# 2021-07-02_OrangeHat.net
KiCad netlist of a schematic drawn in EAGLE
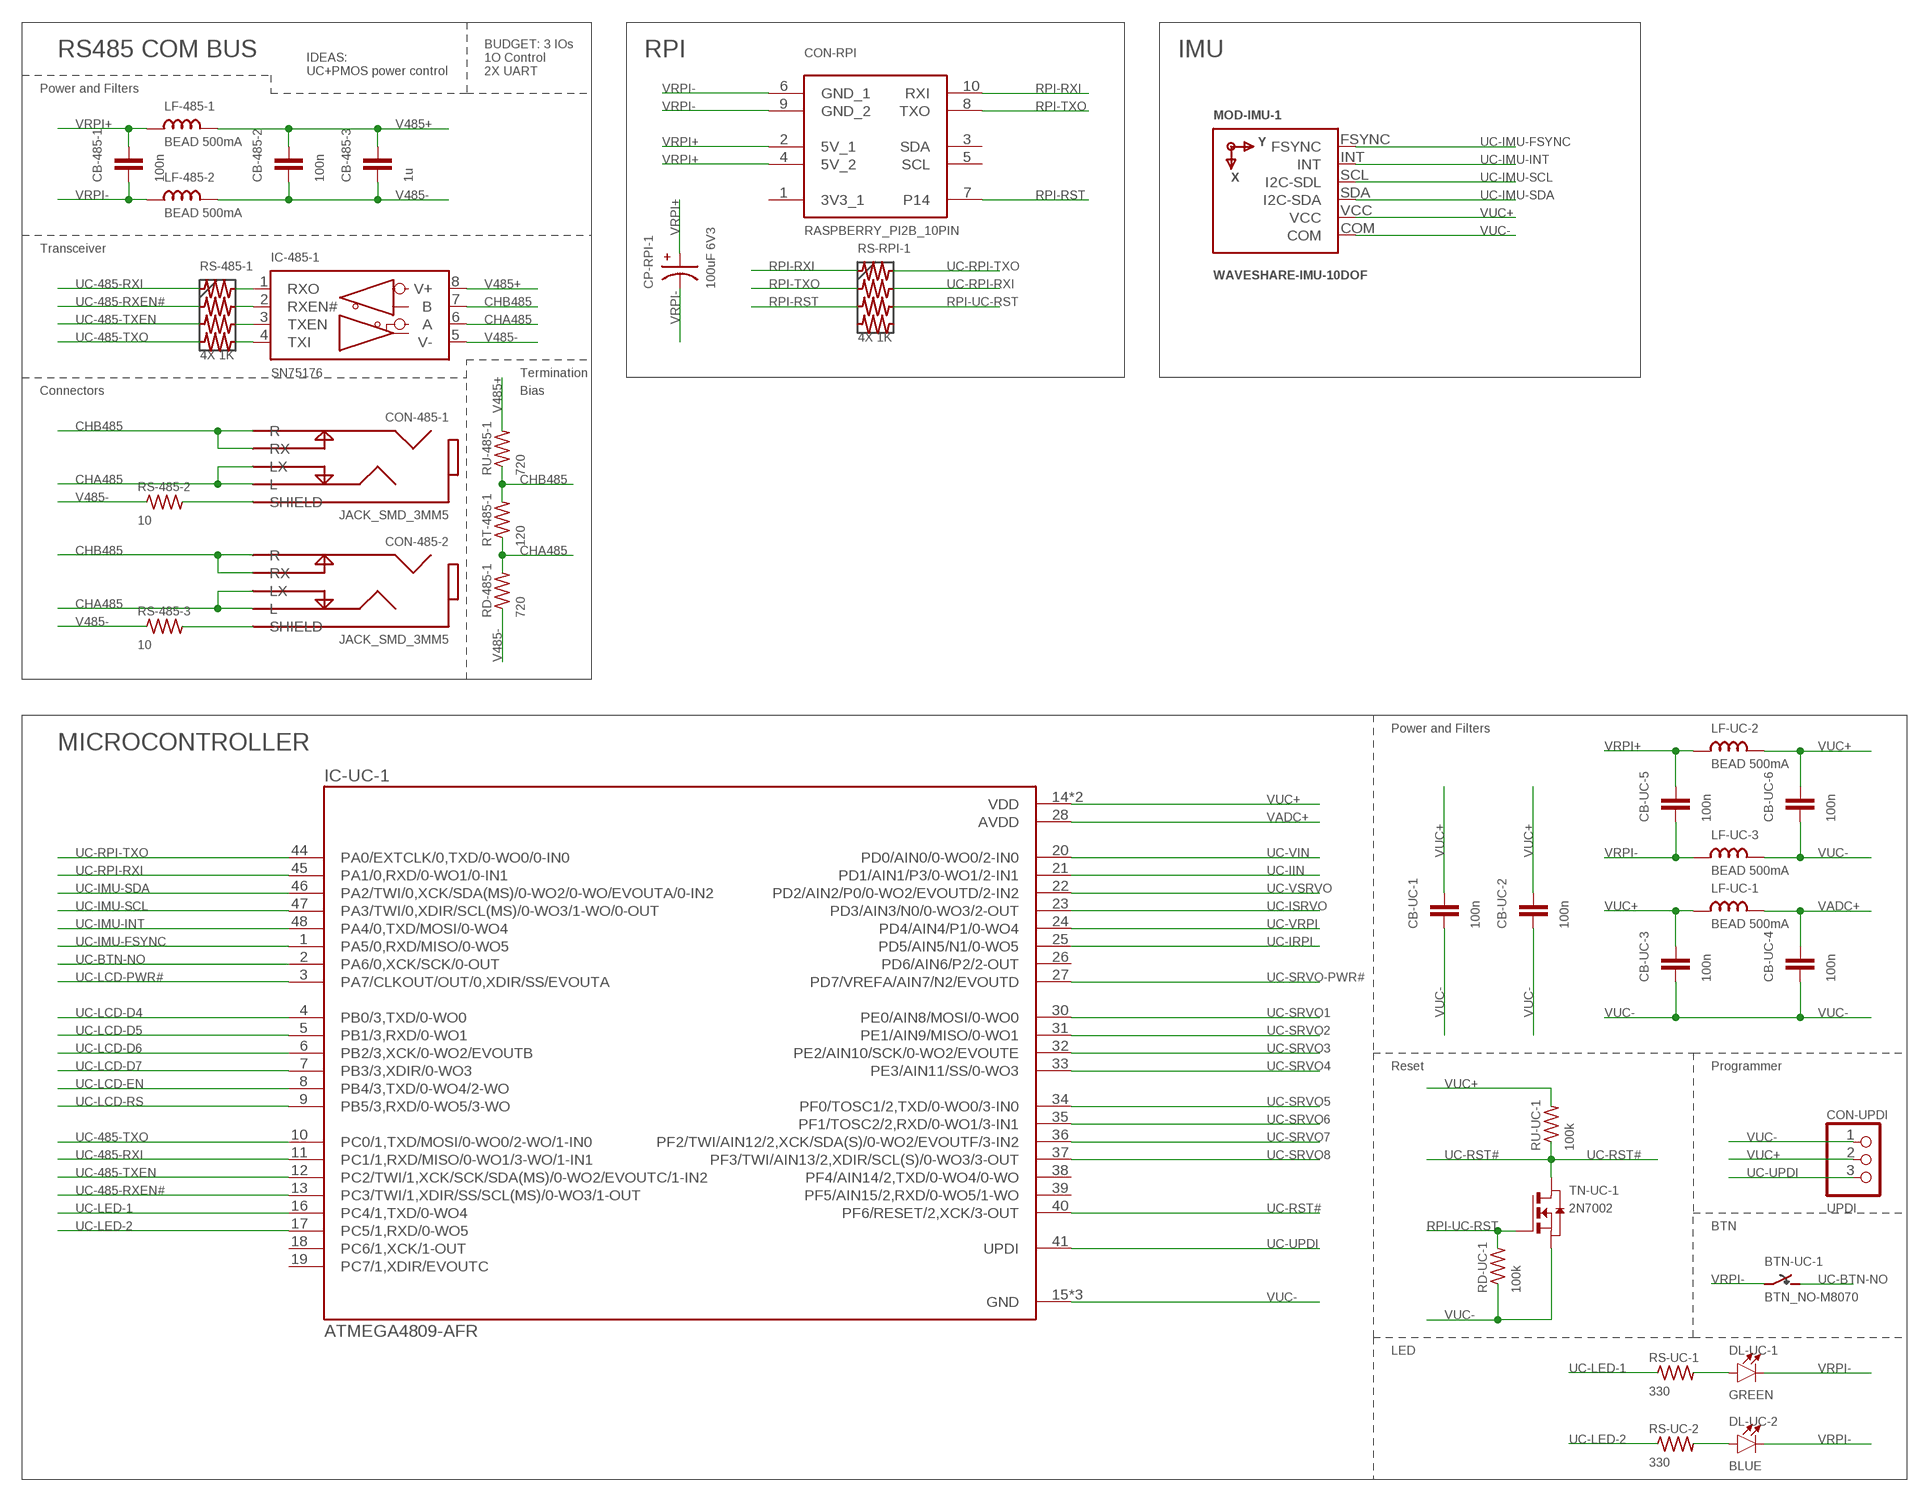
[diagram p0: schematic, sheet 1, part 1 of 2]
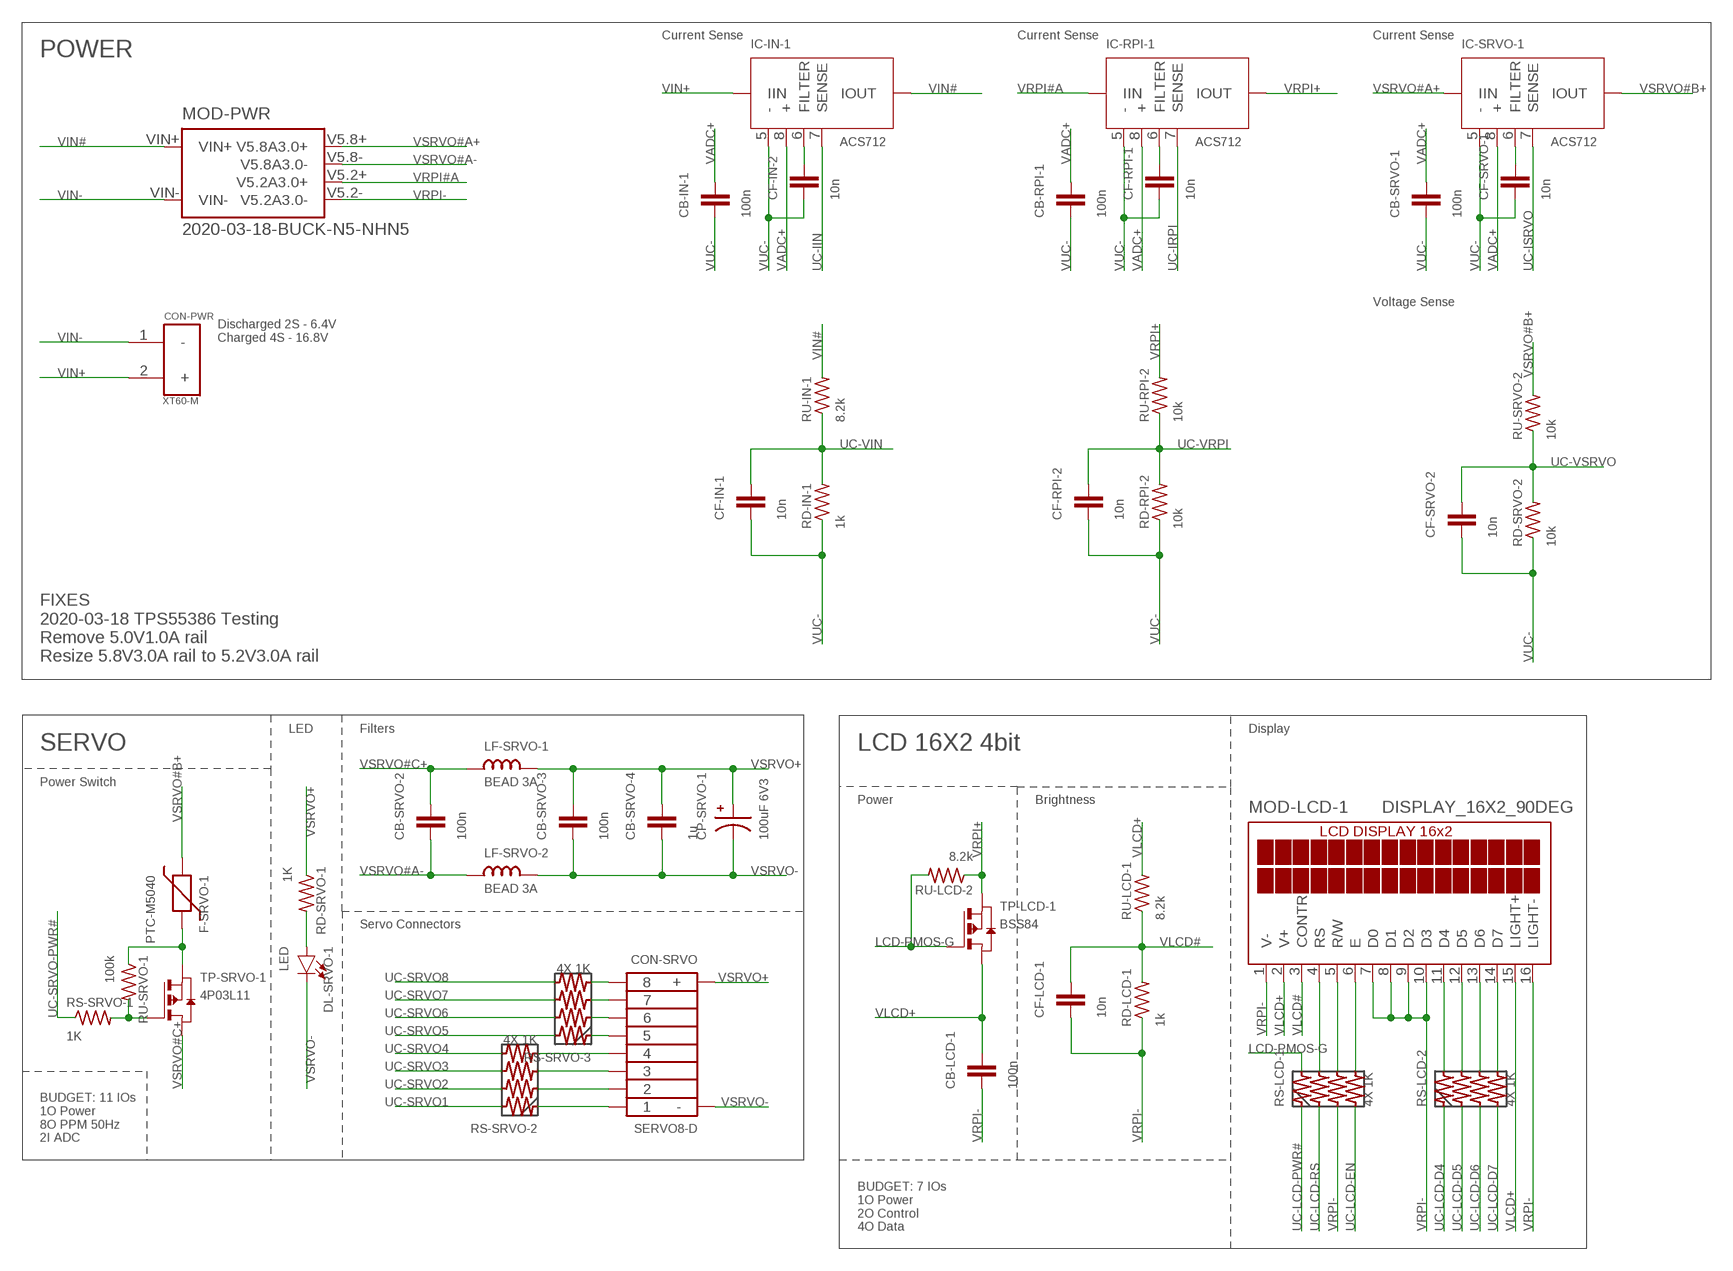
[diagram p1: schematic, sheet 1, part 2 of 2]

(export (version "E")
  (design (tool "Eeschema 10.0.6"))
  (components
    (comp (ref "BTN-UC-1")
      (value "BTN_NO-M8070")
      (footprint "eagle-import:SMD_BTN_M8070")
      (libsource (lib "eagle-import") (part "BTN_NO-M8070"))
    )
    (comp (ref "CB-485-1")
      (value "100n")
      (footprint "eagle-import:SMD-M2012")
      (libsource (lib "eagle-import") (part "C-NPOL"))
    )
    (comp (ref "CB-485-2")
      (value "100n")
      (footprint "eagle-import:SMD-M2012")
      (libsource (lib "eagle-import") (part "C-NPOL"))
    )
    (comp (ref "CB-485-3")
      (value "1u")
      (footprint "eagle-import:SMD-M2012")
      (libsource (lib "eagle-import") (part "C-NPOL"))
    )
    (comp (ref "CB-IN-1")
      (value "100n")
      (footprint "eagle-import:SMD-M2012")
      (libsource (lib "eagle-import") (part "C-NPOL"))
    )
    (comp (ref "CB-LCD-1")
      (value "100n")
      (footprint "eagle-import:SMD-M2012")
      (libsource (lib "eagle-import") (part "C-NPOL"))
    )
    (comp (ref "CB-RPI-1")
      (value "100n")
      (footprint "eagle-import:SMD-M2012")
      (libsource (lib "eagle-import") (part "C-NPOL"))
    )
    (comp (ref "CB-SRVO-1")
      (value "100n")
      (footprint "eagle-import:SMD-M2012")
      (libsource (lib "eagle-import") (part "C-NPOL"))
    )
    (comp (ref "CB-SRVO-2")
      (value "100n")
      (footprint "eagle-import:SMD-M2012")
      (libsource (lib "eagle-import") (part "C-NPOL"))
    )
    (comp (ref "CB-SRVO-3")
      (value "100n")
      (footprint "eagle-import:SMD-M2012")
      (libsource (lib "eagle-import") (part "C-NPOL"))
    )
    (comp (ref "CB-SRVO-4")
      (value "1u")
      (footprint "eagle-import:SMD-M2012")
      (libsource (lib "eagle-import") (part "C-NPOL"))
    )
    (comp (ref "CB-UC-1")
      (value "100n")
      (footprint "eagle-import:SMD-M2012")
      (libsource (lib "eagle-import") (part "C-NPOL"))
    )
    (comp (ref "CB-UC-2")
      (value "100n")
      (footprint "eagle-import:SMD-M2012")
      (libsource (lib "eagle-import") (part "C-NPOL"))
    )
    (comp (ref "CB-UC-3")
      (value "100n")
      (footprint "eagle-import:SMD-M2012")
      (libsource (lib "eagle-import") (part "C-NPOL"))
    )
    (comp (ref "CB-UC-4")
      (value "100n")
      (footprint "eagle-import:SMD-M2012")
      (libsource (lib "eagle-import") (part "C-NPOL"))
    )
    (comp (ref "CB-UC-5")
      (value "100n")
      (footprint "eagle-import:SMD-M2012")
      (libsource (lib "eagle-import") (part "C-NPOL"))
    )
    (comp (ref "CB-UC-6")
      (value "100n")
      (footprint "eagle-import:SMD-M2012")
      (libsource (lib "eagle-import") (part "C-NPOL"))
    )
    (comp (ref "CF-IN-1")
      (value "10n")
      (footprint "eagle-import:SMD-M2012")
      (libsource (lib "eagle-import") (part "C-NPOL"))
    )
    (comp (ref "CF-IN-2")
      (value "10n")
      (footprint "eagle-import:SMD-M2012")
      (libsource (lib "eagle-import") (part "C-NPOL"))
    )
    (comp (ref "CF-LCD-1")
      (value "10n")
      (footprint "eagle-import:SMD-M2012")
      (libsource (lib "eagle-import") (part "C-NPOL"))
    )
    (comp (ref "CF-RPI-1")
      (value "10n")
      (footprint "eagle-import:SMD-M2012")
      (libsource (lib "eagle-import") (part "C-NPOL"))
    )
    (comp (ref "CF-RPI-2")
      (value "10n")
      (footprint "eagle-import:SMD-M2012")
      (libsource (lib "eagle-import") (part "C-NPOL"))
    )
    (comp (ref "CF-SRVO-1")
      (value "10n")
      (footprint "eagle-import:SMD-M2012")
      (libsource (lib "eagle-import") (part "C-NPOL"))
    )
    (comp (ref "CF-SRVO-2")
      (value "10n")
      (footprint "eagle-import:SMD-M2012")
      (libsource (lib "eagle-import") (part "C-NPOL"))
    )
    (comp (ref "CON-485-1")
      (value "JACK_SMD_3MM5")
      (footprint "eagle-import:JACK_SMD_3MM5")
      (libsource (lib "eagle-import") (part "JACK_SMD_3MM5"))
    )
    (comp (ref "CON-485-2")
      (value "JACK_SMD_3MM5")
      (footprint "eagle-import:JACK_SMD_3MM5")
      (libsource (lib "eagle-import") (part "JACK_SMD_3MM5"))
    )
    (comp (ref "CON-PWR")
      (value "XT60-M")
      (footprint "eagle-import:AMASS_XT60-M")
      (fields (field (name "MF") "AMASS"))
      (libsource (lib "eagle-import") (part "XT60-M"))
    )
    (comp (ref "CON-RPI")
      (value "RASPBERRY_PI2B_10PIN")
      (footprint "eagle-import:RASPBERRY_PI2B_10PIN")
      (libsource (lib "eagle-import") (part "RASPBERRY_PI2B_10PIN"))
    )
    (comp (ref "CON-SRVO")
      (value "SERVO8-D")
      (footprint "eagle-import:SERVO8#")
      (libsource (lib "eagle-import") (part "SERVO8-D"))
    )
    (comp (ref "CON-UPDI")
      (value "UPDI")
      (footprint "eagle-import:1X03")
      (libsource (lib "eagle-import") (part "PINHD-1X3"))
    )
    (comp (ref "CP-RPI-1")
      (value "100uF 6V3")
      (footprint "eagle-import:E2,5-5")
      (libsource (lib "eagle-import") (part "C-POLE2.5-5"))
    )
    (comp (ref "CP-SRVO-1")
      (value "100uF 6V3")
      (footprint "eagle-import:E2,5-5")
      (libsource (lib "eagle-import") (part "C-POLE2.5-5"))
    )
    (comp (ref "DL-SRVO-1")
      (value "LED")
      (footprint "eagle-import:SMD-M2012-POL")
      (libsource (lib "eagle-import") (part "LED"))
    )
    (comp (ref "DL-UC-1")
      (value "GREEN")
      (footprint "eagle-import:SMD-M2012-POL")
      (libsource (lib "eagle-import") (part "LED"))
    )
    (comp (ref "DL-UC-2")
      (value "BLUE")
      (footprint "eagle-import:SMD-M2012-POL")
      (libsource (lib "eagle-import") (part "LED"))
    )
    (comp (ref "F-SRVO-1")
      (value "PTC-M5040")
      (footprint "eagle-import:SMD-M5040")
      (libsource (lib "eagle-import") (part "PTC-M5040"))
    )
    (comp (ref "IC-485-1")
      (value "SN75176")
      (footprint "eagle-import:DIL08")
      (fields (field (name "MPN") "MAX481CPA+"))
      (libsource (lib "eagle-import") (part "RS485"))
    )
    (comp (ref "IC-IN-1")
      (value "ACS712")
      (footprint "eagle-import:SO8")
      (libsource (lib "eagle-import") (part "ACS712"))
    )
    (comp (ref "IC-RPI-1")
      (value "ACS712")
      (footprint "eagle-import:SO8")
      (libsource (lib "eagle-import") (part "ACS712"))
    )
    (comp (ref "IC-SRVO-1")
      (value "ACS712")
      (footprint "eagle-import:SO8")
      (libsource (lib "eagle-import") (part "ACS712"))
    )
    (comp (ref "IC-UC-1")
      (value "ATMEGA4809-AFR")
      (footprint "eagle-import:QFP50P900X900X120-48N")
      (fields (field (name "MF") "Microchip"))
      (libsource (lib "eagle-import") (part "ATMEGA4809-AFR"))
    )
    (comp (ref "LF-485-1")
      (value "BEAD 500mA")
      (footprint "eagle-import:SMD-M2012")
      (libsource (lib "eagle-import") (part "L-M2012"))
    )
    (comp (ref "LF-485-2")
      (value "BEAD 500mA")
      (footprint "eagle-import:SMD-M2012")
      (libsource (lib "eagle-import") (part "L-M2012"))
    )
    (comp (ref "LF-SRVO-1")
      (value "BEAD 3A")
      (footprint "eagle-import:SMD-M2016")
      (libsource (lib "eagle-import") (part "L-M2016"))
    )
    (comp (ref "LF-SRVO-2")
      (value "BEAD 3A")
      (footprint "eagle-import:SMD-M2016")
      (libsource (lib "eagle-import") (part "L-M2016"))
    )
    (comp (ref "LF-UC-1")
      (value "BEAD 500mA")
      (footprint "eagle-import:SMD-M2012")
      (libsource (lib "eagle-import") (part "L-M2012"))
    )
    (comp (ref "LF-UC-2")
      (value "BEAD 500mA")
      (footprint "eagle-import:SMD-M2012")
      (libsource (lib "eagle-import") (part "L-M2012"))
    )
    (comp (ref "LF-UC-3")
      (value "BEAD 500mA")
      (footprint "eagle-import:SMD-M2012")
      (libsource (lib "eagle-import") (part "L-M2012"))
    )
    (comp (ref "MOD-IMU-1")
      (value "WAVESHARE-IMU-10DOF")
      (footprint "eagle-import:WAVESHARE-IMU-10DOF")
      (libsource (lib "eagle-import") (part "WAVESHARE-IMU-10DOF"))
    )
    (comp (ref "MOD-LCD-1")
      (value "DISPLAY_16X2_90DEG")
      (footprint "eagle-import:DISPLAY_16X2_90DEG")
      (libsource (lib "eagle-import") (part "DISPLAY_16X2_90DEG"))
    )
    (comp (ref "MOD-PWR")
      (value "2020-03-18-BUCK-N5-NHN5")
      (footprint "eagle-import:2020-03-18-BUCK-NHN5")
      (libsource (lib "eagle-import") (part "2020-03-18-BUCK-N5-NHN5"))
    )
    (comp (ref "RD-485-1")
      (value "720")
      (footprint "eagle-import:TH-2MM54-V")
      (libsource (lib "eagle-import") (part "R0207/2V"))
    )
    (comp (ref "RD-IN-1")
      (value "1k")
      (footprint "eagle-import:SMD-M2012")
      (libsource (lib "eagle-import") (part "R-M2012"))
    )
    (comp (ref "RD-LCD-1")
      (value "1k")
      (footprint "eagle-import:SMD-M2012")
      (libsource (lib "eagle-import") (part "R-M2012"))
    )
    (comp (ref "RD-RPI-2")
      (value "10k")
      (footprint "eagle-import:SMD-M2012")
      (libsource (lib "eagle-import") (part "R-M2012"))
    )
    (comp (ref "RD-SRVO-1")
      (value "1K")
      (footprint "eagle-import:SMD-M2012")
      (libsource (lib "eagle-import") (part "R-M2012"))
    )
    (comp (ref "RD-SRVO-2")
      (value "10k")
      (footprint "eagle-import:SMD-M2012")
      (libsource (lib "eagle-import") (part "R-M2012"))
    )
    (comp (ref "RD-UC-1")
      (value "100k")
      (footprint "eagle-import:SMD-M2012")
      (libsource (lib "eagle-import") (part "R-M2012"))
    )
    (comp (ref "RS-485-1")
      (value "4X 1K")
      (footprint "eagle-import:RAC1206")
      (libsource (lib "eagle-import") (part "RAC164"))
    )
    (comp (ref "RS-485-2")
      (value "10")
      (footprint "eagle-import:SMD-M2012")
      (libsource (lib "eagle-import") (part "R-M2012"))
    )
    (comp (ref "RS-485-3")
      (value "10")
      (footprint "eagle-import:SMD-M2012")
      (libsource (lib "eagle-import") (part "R-M2012"))
    )
    (comp (ref "RS-LCD-1")
      (value "4X 1K")
      (footprint "eagle-import:RAC1206")
      (libsource (lib "eagle-import") (part "RAC164"))
    )
    (comp (ref "RS-LCD-2")
      (value "4X 1K")
      (footprint "eagle-import:RAC1206")
      (libsource (lib "eagle-import") (part "RAC164"))
    )
    (comp (ref "RS-RPI-1")
      (value "4X 1K")
      (footprint "eagle-import:RAC1206")
      (libsource (lib "eagle-import") (part "RAC164"))
    )
    (comp (ref "RS-SRVO-1")
      (value "1K")
      (footprint "eagle-import:SMD-M2012")
      (libsource (lib "eagle-import") (part "R-M2012"))
    )
    (comp (ref "RS-SRVO-2")
      (value "4X 1K")
      (footprint "eagle-import:RAC1206")
      (libsource (lib "eagle-import") (part "RAC164"))
    )
    (comp (ref "RS-SRVO-3")
      (value "4X 1K")
      (footprint "eagle-import:RAC1206")
      (libsource (lib "eagle-import") (part "RAC164"))
    )
    (comp (ref "RS-UC-1")
      (value "330")
      (footprint "eagle-import:SMD-M2012")
      (libsource (lib "eagle-import") (part "R-M2012"))
    )
    (comp (ref "RS-UC-2")
      (value "330")
      (footprint "eagle-import:SMD-M2012")
      (libsource (lib "eagle-import") (part "R-M2012"))
    )
    (comp (ref "RT-485-1")
      (value "120")
      (footprint "eagle-import:TH-2MM54-V")
      (libsource (lib "eagle-import") (part "R0207/2V"))
    )
    (comp (ref "RU-485-1")
      (value "720")
      (footprint "eagle-import:TH-2MM54-V")
      (libsource (lib "eagle-import") (part "R0207/2V"))
    )
    (comp (ref "RU-IN-1")
      (value "8.2k")
      (footprint "eagle-import:SMD-M2012")
      (libsource (lib "eagle-import") (part "R-M2012"))
    )
    (comp (ref "RU-LCD-1")
      (value "8.2k")
      (footprint "eagle-import:SMD-M2012")
      (libsource (lib "eagle-import") (part "R-M2012"))
    )
    (comp (ref "RU-LCD-2")
      (value "8.2k")
      (footprint "eagle-import:SMD-M2012")
      (libsource (lib "eagle-import") (part "R-M2012"))
    )
    (comp (ref "RU-RPI-2")
      (value "10k")
      (footprint "eagle-import:SMD-M2012")
      (libsource (lib "eagle-import") (part "R-M2012"))
    )
    (comp (ref "RU-SRVO-1")
      (value "100k")
      (footprint "eagle-import:SMD-M2012")
      (libsource (lib "eagle-import") (part "R-M2012"))
    )
    (comp (ref "RU-SRVO-2")
      (value "10k")
      (footprint "eagle-import:SMD-M2012")
      (libsource (lib "eagle-import") (part "R-M2012"))
    )
    (comp (ref "RU-UC-1")
      (value "100k")
      (footprint "eagle-import:SMD-M2012")
      (libsource (lib "eagle-import") (part "R-M2012"))
    )
    (comp (ref "TN-UC-1")
      (value "2N7002")
      (footprint "eagle-import:SOT23")
      (libsource (lib "eagle-import") (part "MOS-N-SOT23"))
    )
    (comp (ref "TP-LCD-1")
      (value "BSS84")
      (footprint "eagle-import:SOT23")
      (libsource (lib "eagle-import") (part "MOS-P-SOT23"))
    )
    (comp (ref "TP-SRVO-1")
      (value "4P03L11")
      (footprint "eagle-import:TO252")
      (libsource (lib "eagle-import") (part "MOS-P-TO252"))
    )
  )
  (nets
    (net (code "1") (name "/3V3_1") (class "Default")
      (node (ref "CON-RPI") (pin "1") (pinfunction "3V3_1_1") (pintype "power_in"))
    )
    (net (code "2") (name "/CHA485") (class "Default")
      (node (ref "CON-485-1") (pin "L") (pinfunction "L_L") (pintype "bidirectional"))
      (node (ref "CON-485-1") (pin "LX") (pinfunction "LX_LX") (pintype "bidirectional"))
      (node (ref "CON-485-2") (pin "L") (pinfunction "L_L") (pintype "bidirectional"))
      (node (ref "CON-485-2") (pin "LX") (pinfunction "LX_LX") (pintype "bidirectional"))
      (node (ref "IC-485-1") (pin "6") (pinfunction "A_6") (pintype "passive"))
      (node (ref "RD-485-1") (pin "2") (pinfunction "2_2") (pintype "passive"))
      (node (ref "RT-485-1") (pin "1") (pinfunction "1_1") (pintype "passive"))
    )
    (net (code "3") (name "/CHB485") (class "Default")
      (node (ref "CON-485-1") (pin "R") (pinfunction "R_R") (pintype "bidirectional"))
      (node (ref "CON-485-1") (pin "RX") (pinfunction "RX_RX") (pintype "bidirectional"))
      (node (ref "CON-485-2") (pin "R") (pinfunction "R_R") (pintype "bidirectional"))
      (node (ref "CON-485-2") (pin "RX") (pinfunction "RX_RX") (pintype "bidirectional"))
      (node (ref "IC-485-1") (pin "7") (pinfunction "B_7") (pintype "passive"))
      (node (ref "RT-485-1") (pin "2") (pinfunction "2_2") (pintype "passive"))
      (node (ref "RU-485-1") (pin "1") (pinfunction "1_1") (pintype "passive"))
    )
    (net (code "4") (name "/LCD-PMOS-G") (class "Default")
      (node (ref "RS-LCD-1") (pin "1B") (pinfunction "1B_1B") (pintype "bidirectional"))
      (node (ref "RU-LCD-2") (pin "2") (pinfunction "2_2") (pintype "passive"))
      (node (ref "TP-LCD-1") (pin "1") (pinfunction "G_1") (pintype "passive"))
    )
    (net (code "5") (name "/RPI-RST") (class "Default")
      (node (ref "CON-RPI") (pin "7") (pinfunction "P14_7") (pintype "bidirectional"))
      (node (ref "RS-RPI-1") (pin "3A") (pinfunction "3A_3A") (pintype "bidirectional"))
    )
    (net (code "6") (name "/RPI-RXI") (class "Default")
      (node (ref "CON-RPI") (pin "10") (pinfunction "RXI_10") (pintype "bidirectional"))
      (node (ref "RS-RPI-1") (pin "1A") (pinfunction "1A_1A") (pintype "bidirectional"))
    )
    (net (code "7") (name "/RPI-TXO") (class "Default")
      (node (ref "CON-RPI") (pin "8") (pinfunction "TXO_8") (pintype "bidirectional"))
      (node (ref "RS-RPI-1") (pin "2A") (pinfunction "2A_2A") (pintype "bidirectional"))
    )
    (net (code "8") (name "/RPI-UC-RST") (class "Default")
      (node (ref "RD-UC-1") (pin "2") (pinfunction "2_2") (pintype "passive"))
      (node (ref "RS-RPI-1") (pin "3B") (pinfunction "3B_3B") (pintype "bidirectional"))
      (node (ref "TN-UC-1") (pin "1") (pinfunction "G_1") (pintype "passive"))
    )
    (net (code "9") (name "/UC-485-RXEN#") (class "Default")
      (node (ref "IC-UC-1") (pin "13") (pinfunction "PC3/TWI/1,XDIR/SS/SCL(MS)/0-WO3/1-OUT_13") (pintype "bidirectional"))
      (node (ref "RS-485-1") (pin "2A") (pinfunction "2A_2A") (pintype "bidirectional"))
    )
    (net (code "10") (name "/UC-485-RXI") (class "Default")
      (node (ref "IC-UC-1") (pin "11") (pinfunction "PC1/1,RXD/MISO/0-WO1/3-WO/1-IN1_11") (pintype "bidirectional"))
      (node (ref "RS-485-1") (pin "1A") (pinfunction "1A_1A") (pintype "bidirectional"))
    )
    (net (code "11") (name "/UC-485-TXEN") (class "Default")
      (node (ref "IC-UC-1") (pin "12") (pinfunction "PC2/TWI/1,XCK/SCK/SDA(MS)/0-WO2/EVOUTC/1-IN2_12") (pintype "bidirectional"))
      (node (ref "RS-485-1") (pin "3A") (pinfunction "3A_3A") (pintype "bidirectional"))
    )
    (net (code "12") (name "/UC-485-TXO") (class "Default")
      (node (ref "IC-UC-1") (pin "10") (pinfunction "PC0/1,TXD/MOSI/0-WO0/2-WO/1-IN0_10") (pintype "bidirectional"))
      (node (ref "RS-485-1") (pin "4A") (pinfunction "4A_4A") (pintype "bidirectional"))
    )
    (net (code "13") (name "/UC-BTN-NO") (class "Default")
      (node (ref "BTN-UC-1") (pin "2B") (pinfunction "P$2_2B") (pintype "passive"))
      (node (ref "BTN-UC-1") (pin "3B") (pinfunction "P$2_3B") (pintype "passive"))
      (node (ref "IC-UC-1") (pin "2") (pinfunction "PA6/0,XCK/SCK/0-OUT_2") (pintype "bidirectional"))
    )
    (net (code "14") (name "/UC-IIN") (class "Default")
      (node (ref "IC-IN-1") (pin "7") (pinfunction "SENSE_7") (pintype "output"))
      (node (ref "IC-UC-1") (pin "21") (pinfunction "PD1/AIN1/P3/0-WO1/2-IN1_21") (pintype "bidirectional"))
    )
    (net (code "15") (name "/UC-IMU-FSYNC") (class "Default")
      (node (ref "IC-UC-1") (pin "1") (pinfunction "PA5/0,RXD/MISO/0-WO5_1") (pintype "bidirectional"))
      (node (ref "MOD-IMU-1") (pin "FSYNC") (pinfunction "FSYNC_FSYNC") (pintype "bidirectional"))
    )
    (net (code "16") (name "/UC-IMU-INT") (class "Default")
      (node (ref "IC-UC-1") (pin "48") (pinfunction "PA4/0,TXD/MOSI/0-WO4_48") (pintype "bidirectional"))
      (node (ref "MOD-IMU-1") (pin "INT") (pinfunction "INT_INT") (pintype "bidirectional"))
    )
    (net (code "17") (name "/UC-IMU-SCL") (class "Default")
      (node (ref "IC-UC-1") (pin "47") (pinfunction "PA3/TWI/0,XDIR/SCL(MS)/0-WO3/1-WO/0-OUT_47") (pintype "bidirectional"))
      (node (ref "MOD-IMU-1") (pin "SCL") (pinfunction "I2C-SDL_SCL") (pintype "bidirectional"))
    )
    (net (code "18") (name "/UC-IMU-SDA") (class "Default")
      (node (ref "IC-UC-1") (pin "46") (pinfunction "PA2/TWI/0,XCK/SDA(MS)/0-WO2/0-WO/EVOUTA/0-IN2_46") (pintype "bidirectional"))
      (node (ref "MOD-IMU-1") (pin "SDA") (pinfunction "I2C-SDA_SDA") (pintype "bidirectional"))
    )
    (net (code "19") (name "/UC-IRPI") (class "Default")
      (node (ref "IC-RPI-1") (pin "7") (pinfunction "SENSE_7") (pintype "output"))
      (node (ref "IC-UC-1") (pin "25") (pinfunction "PD5/AIN5/N1/0-WO5_25") (pintype "bidirectional"))
    )
    (net (code "20") (name "/UC-ISRVO") (class "Default")
      (node (ref "IC-SRVO-1") (pin "7") (pinfunction "SENSE_7") (pintype "output"))
      (node (ref "IC-UC-1") (pin "23") (pinfunction "PD3/AIN3/N0/0-WO3/2-OUT_23") (pintype "bidirectional"))
    )
    (net (code "21") (name "/UC-LCD-D4") (class "Default")
      (node (ref "IC-UC-1") (pin "4") (pinfunction "PB0/3,TXD/0-WO0_4") (pintype "bidirectional"))
      (node (ref "RS-LCD-2") (pin "1A") (pinfunction "1A_1A") (pintype "bidirectional"))
    )
    (net (code "22") (name "/UC-LCD-D5") (class "Default")
      (node (ref "IC-UC-1") (pin "5") (pinfunction "PB1/3,RXD/0-WO1_5") (pintype "bidirectional"))
      (node (ref "RS-LCD-2") (pin "2A") (pinfunction "2A_2A") (pintype "bidirectional"))
    )
    (net (code "23") (name "/UC-LCD-D6") (class "Default")
      (node (ref "IC-UC-1") (pin "6") (pinfunction "PB2/3,XCK/0-WO2/EVOUTB_6") (pintype "bidirectional"))
      (node (ref "RS-LCD-2") (pin "3A") (pinfunction "3A_3A") (pintype "bidirectional"))
    )
    (net (code "24") (name "/UC-LCD-D7") (class "Default")
      (node (ref "IC-UC-1") (pin "7") (pinfunction "PB3/3,XDIR/0-WO3_7") (pintype "bidirectional"))
      (node (ref "RS-LCD-2") (pin "4A") (pinfunction "4A_4A") (pintype "bidirectional"))
    )
    (net (code "25") (name "/UC-LCD-EN") (class "Default")
      (node (ref "IC-UC-1") (pin "8") (pinfunction "PB4/3,TXD/0-WO4/2-WO_8") (pintype "bidirectional"))
      (node (ref "RS-LCD-1") (pin "4A") (pinfunction "4A_4A") (pintype "bidirectional"))
    )
    (net (code "26") (name "/UC-LCD-PWR#") (class "Default")
      (node (ref "IC-UC-1") (pin "3") (pinfunction "PA7/CLKOUT/OUT/0,XDIR/SS/EVOUTA_3") (pintype "bidirectional"))
      (node (ref "RS-LCD-1") (pin "1A") (pinfunction "1A_1A") (pintype "bidirectional"))
    )
    (net (code "27") (name "/UC-LCD-RS") (class "Default")
      (node (ref "IC-UC-1") (pin "9") (pinfunction "PB5/3,RXD/0-WO5/3-WO_9") (pintype "bidirectional"))
      (node (ref "RS-LCD-1") (pin "2A") (pinfunction "2A_2A") (pintype "bidirectional"))
    )
    (net (code "28") (name "/UC-LED-1") (class "Default")
      (node (ref "IC-UC-1") (pin "16") (pinfunction "PC4/1,TXD/0-WO4_16") (pintype "bidirectional"))
      (node (ref "RS-UC-1") (pin "1") (pinfunction "1_1") (pintype "passive"))
    )
    (net (code "29") (name "/UC-LED-2") (class "Default")
      (node (ref "IC-UC-1") (pin "17") (pinfunction "PC5/1,RXD/0-WO5_17") (pintype "bidirectional"))
      (node (ref "RS-UC-2") (pin "1") (pinfunction "1_1") (pintype "passive"))
    )
    (net (code "30") (name "/UC-RPI-RXI") (class "Default")
      (node (ref "IC-UC-1") (pin "45") (pinfunction "PA1/0,RXD/0-WO1/0-IN1_45") (pintype "bidirectional"))
      (node (ref "RS-RPI-1") (pin "2B") (pinfunction "2B_2B") (pintype "bidirectional"))
    )
    (net (code "31") (name "/UC-RPI-TXO") (class "Default")
      (node (ref "IC-UC-1") (pin "44") (pinfunction "PA0/EXTCLK/0,TXD/0-WO0/0-IN0_44") (pintype "bidirectional"))
      (node (ref "RS-RPI-1") (pin "1B") (pinfunction "1B_1B") (pintype "bidirectional"))
    )
    (net (code "32") (name "/UC-RST#") (class "Default")
      (node (ref "IC-UC-1") (pin "40") (pinfunction "PF6/RESET/2,XCK/3-OUT_40") (pintype "bidirectional"))
      (node (ref "RU-UC-1") (pin "1") (pinfunction "1_1") (pintype "passive"))
      (node (ref "TN-UC-1") (pin "3") (pinfunction "D_3") (pintype "passive"))
    )
    (net (code "33") (name "/UC-SRVO-PWR#") (class "Default")
      (node (ref "IC-UC-1") (pin "27") (pinfunction "PD7/VREFA/AIN7/N2/EVOUTD_27") (pintype "bidirectional"))
      (node (ref "RS-SRVO-1") (pin "1") (pinfunction "1_1") (pintype "passive"))
    )
    (net (code "34") (name "/UC-SRVO1") (class "Default")
      (node (ref "IC-UC-1") (pin "30") (pinfunction "PE0/AIN8/MOSI/0-WO0_30") (pintype "bidirectional"))
      (node (ref "RS-SRVO-2") (pin "1B") (pinfunction "1B_1B") (pintype "bidirectional"))
    )
    (net (code "35") (name "/UC-SRVO2") (class "Default")
      (node (ref "IC-UC-1") (pin "31") (pinfunction "PE1/AIN9/MISO/0-WO1_31") (pintype "bidirectional"))
      (node (ref "RS-SRVO-2") (pin "2B") (pinfunction "2B_2B") (pintype "bidirectional"))
    )
    (net (code "36") (name "/UC-SRVO3") (class "Default")
      (node (ref "IC-UC-1") (pin "32") (pinfunction "PE2/AIN10/SCK/0-WO2/EVOUTE_32") (pintype "bidirectional"))
      (node (ref "RS-SRVO-2") (pin "3B") (pinfunction "3B_3B") (pintype "bidirectional"))
    )
    (net (code "37") (name "/UC-SRVO4") (class "Default")
      (node (ref "IC-UC-1") (pin "33") (pinfunction "PE3/AIN11/SS/0-WO3_33") (pintype "bidirectional"))
      (node (ref "RS-SRVO-2") (pin "4B") (pinfunction "4B_4B") (pintype "bidirectional"))
    )
    (net (code "38") (name "/UC-SRVO5") (class "Default")
      (node (ref "IC-UC-1") (pin "34") (pinfunction "PF0/TOSC1/2,TXD/0-WO0/3-IN0_34") (pintype "bidirectional"))
      (node (ref "RS-SRVO-3") (pin "1B") (pinfunction "1B_1B") (pintype "bidirectional"))
    )
    (net (code "39") (name "/UC-SRVO6") (class "Default")
      (node (ref "IC-UC-1") (pin "35") (pinfunction "PF1/TOSC2/2,RXD/0-WO1/3-IN1_35") (pintype "bidirectional"))
      (node (ref "RS-SRVO-3") (pin "2B") (pinfunction "2B_2B") (pintype "bidirectional"))
    )
    (net (code "40") (name "/UC-SRVO7") (class "Default")
      (node (ref "IC-UC-1") (pin "36") (pinfunction "PF2/TWI/AIN12/2,XCK/SDA(S)/0-WO2/EVOUTF/3-IN2_36") (pintype "bidirectional"))
      (node (ref "RS-SRVO-3") (pin "3B") (pinfunction "3B_3B") (pintype "bidirectional"))
    )
    (net (code "41") (name "/UC-SRVO8") (class "Default")
      (node (ref "IC-UC-1") (pin "37") (pinfunction "PF3/TWI/AIN13/2,XDIR/SCL(S)/0-WO3/3-OUT_37") (pintype "bidirectional"))
      (node (ref "RS-SRVO-3") (pin "4B") (pinfunction "4B_4B") (pintype "bidirectional"))
    )
    (net (code "42") (name "/UC-UPDI") (class "Default")
      (node (ref "CON-UPDI") (pin "3") (pinfunction "3_3") (pintype "passive"))
      (node (ref "IC-UC-1") (pin "41") (pinfunction "UPDI_41") (pintype "bidirectional"))
    )
    (net (code "43") (name "/UC-VIN") (class "Default")
      (node (ref "CF-IN-1") (pin "2") (pinfunction "2_2") (pintype "passive"))
      (node (ref "IC-UC-1") (pin "20") (pinfunction "PD0/AIN0/0-WO0/2-IN0_20") (pintype "bidirectional"))
      (node (ref "RD-IN-1") (pin "2") (pinfunction "2_2") (pintype "passive"))
      (node (ref "RU-IN-1") (pin "1") (pinfunction "1_1") (pintype "passive"))
    )
    (net (code "44") (name "/UC-VRPI") (class "Default")
      (node (ref "CF-RPI-2") (pin "2") (pinfunction "2_2") (pintype "passive"))
      (node (ref "IC-UC-1") (pin "24") (pinfunction "PD4/AIN4/P1/0-WO4_24") (pintype "bidirectional"))
      (node (ref "RD-RPI-2") (pin "2") (pinfunction "2_2") (pintype "passive"))
      (node (ref "RU-RPI-2") (pin "1") (pinfunction "1_1") (pintype "passive"))
    )
    (net (code "45") (name "/UC-VSRVO") (class "Default")
      (node (ref "CF-SRVO-2") (pin "2") (pinfunction "2_2") (pintype "passive"))
      (node (ref "IC-UC-1") (pin "22") (pinfunction "PD2/AIN2/P0/0-WO2/EVOUTD/2-IN2_22") (pintype "bidirectional"))
      (node (ref "RD-SRVO-2") (pin "2") (pinfunction "2_2") (pintype "passive"))
      (node (ref "RU-SRVO-2") (pin "1") (pinfunction "1_1") (pintype "passive"))
    )
    (net (code "46") (name "/V485+") (class "Default")
      (node (ref "CB-485-2") (pin "2") (pinfunction "2_2") (pintype "passive"))
      (node (ref "CB-485-3") (pin "2") (pinfunction "2_2") (pintype "passive"))
      (node (ref "IC-485-1") (pin "8") (pinfunction "V+_8") (pintype "bidirectional"))
      (node (ref "LF-485-1") (pin "2") (pinfunction "2_2") (pintype "passive"))
      (node (ref "RU-485-1") (pin "2") (pinfunction "2_2") (pintype "passive"))
    )
    (net (code "47") (name "/V485-") (class "Default")
      (node (ref "CB-485-2") (pin "1") (pinfunction "1_1") (pintype "passive"))
      (node (ref "CB-485-3") (pin "1") (pinfunction "1_1") (pintype "passive"))
      (node (ref "IC-485-1") (pin "5") (pinfunction "V-_5") (pintype "bidirectional"))
      (node (ref "LF-485-2") (pin "2") (pinfunction "2_2") (pintype "passive"))
      (node (ref "RD-485-1") (pin "1") (pinfunction "1_1") (pintype "passive"))
      (node (ref "RS-485-2") (pin "1") (pinfunction "1_1") (pintype "passive"))
      (node (ref "RS-485-3") (pin "1") (pinfunction "1_1") (pintype "passive"))
    )
    (net (code "48") (name "/VADC+") (class "Default")
      (node (ref "CB-IN-1") (pin "2") (pinfunction "2_2") (pintype "passive"))
      (node (ref "CB-RPI-1") (pin "2") (pinfunction "2_2") (pintype "passive"))
      (node (ref "CB-SRVO-1") (pin "2") (pinfunction "2_2") (pintype "passive"))
      (node (ref "CB-UC-4") (pin "2") (pinfunction "2_2") (pintype "passive"))
      (node (ref "IC-IN-1") (pin "8") (pinfunction "+_8") (pintype "power_in"))
      (node (ref "IC-RPI-1") (pin "8") (pinfunction "+_8") (pintype "power_in"))
      (node (ref "IC-SRVO-1") (pin "8") (pinfunction "+_8") (pintype "power_in"))
      (node (ref "IC-UC-1") (pin "28") (pinfunction "AVDD_28") (pintype "power_in"))
      (node (ref "LF-UC-1") (pin "2") (pinfunction "2_2") (pintype "passive"))
    )
    (net (code "49") (name "/VIN#") (class "Default")
      (node (ref "IC-IN-1") (pin "3") (pinfunction "IOUT_3") (pintype "power_in"))
      (node (ref "IC-IN-1") (pin "4") (pinfunction "IOUT_4") (pintype "power_in"))
      (node (ref "MOD-PWR") (pin "VIN+") (pinfunction "VIN+_VIN+") (pintype "power_in"))
      (node (ref "RU-IN-1") (pin "2") (pinfunction "2_2") (pintype "passive"))
    )
    (net (code "50") (name "/VIN+") (class "Default")
      (node (ref "CON-PWR") (pin "2") (pinfunction "+_2") (pintype "passive"))
      (node (ref "IC-IN-1") (pin "1") (pinfunction "IIN_1") (pintype "power_in"))
      (node (ref "IC-IN-1") (pin "2") (pinfunction "IIN_2") (pintype "power_in"))
    )
    (net (code "51") (name "/VIN-") (class "Default")
      (node (ref "CON-PWR") (pin "1") (pinfunction "-_1") (pintype "passive"))
      (node (ref "MOD-PWR") (pin "VIN-") (pinfunction "VIN-_VIN-") (pintype "power_in"))
    )
    (net (code "52") (name "/VLCD#") (class "Default")
      (node (ref "CF-LCD-1") (pin "2") (pinfunction "2_2") (pintype "passive"))
      (node (ref "MOD-LCD-1") (pin "3") (pinfunction "CONTR_3") (pintype "input"))
      (node (ref "RD-LCD-1") (pin "2") (pinfunction "2_2") (pintype "passive"))
      (node (ref "RU-LCD-1") (pin "1") (pinfunction "1_1") (pintype "passive"))
    )
    (net (code "53") (name "/VLCD+") (class "Default")
      (node (ref "CB-LCD-1") (pin "2") (pinfunction "2_2") (pintype "passive"))
      (node (ref "MOD-LCD-1") (pin "15") (pinfunction "LIGHT+_15") (pintype "power_in"))
      (node (ref "MOD-LCD-1") (pin "2") (pinfunction "V+_2") (pintype "power_in"))
      (node (ref "RU-LCD-1") (pin "2") (pinfunction "2_2") (pintype "passive"))
      (node (ref "TP-LCD-1") (pin "3") (pinfunction "D_3") (pintype "passive"))
    )
    (net (code "54") (name "/VRPI#A") (class "Default")
      (node (ref "IC-RPI-1") (pin "1") (pinfunction "IIN_1") (pintype "power_in"))
      (node (ref "IC-RPI-1") (pin "2") (pinfunction "IIN_2") (pintype "power_in"))
      (node (ref "MOD-PWR") (pin "V5.2+") (pinfunction "V5.2A3.0+_V5.2+") (pintype "power_in"))
    )
    (net (code "55") (name "/VRPI+") (class "Default")
      (node (ref "CB-485-1") (pin "2") (pinfunction "2_2") (pintype "passive"))
      (node (ref "CB-UC-5") (pin "2") (pinfunction "2_2") (pintype "passive"))
      (node (ref "CON-RPI") (pin "2") (pinfunction "5V_1_2") (pintype "power_in"))
      (node (ref "CON-RPI") (pin "4") (pinfunction "5V_2_4") (pintype "power_in"))
      (node (ref "CP-RPI-1") (pin "+") (pinfunction "+_+") (pintype "passive"))
      (node (ref "IC-RPI-1") (pin "3") (pinfunction "IOUT_3") (pintype "power_in"))
      (node (ref "IC-RPI-1") (pin "4") (pinfunction "IOUT_4") (pintype "power_in"))
      (node (ref "LF-485-1") (pin "1") (pinfunction "1_1") (pintype "passive"))
      (node (ref "LF-UC-2") (pin "1") (pinfunction "1_1") (pintype "passive"))
      (node (ref "RU-LCD-2") (pin "1") (pinfunction "1_1") (pintype "passive"))
      (node (ref "RU-RPI-2") (pin "2") (pinfunction "2_2") (pintype "passive"))
      (node (ref "TP-LCD-1") (pin "2") (pinfunction "S_2") (pintype "passive"))
    )
    (net (code "56") (name "/VRPI-") (class "Default")
      (node (ref "BTN-UC-1") (pin "1A") (pinfunction "P$1_1A") (pintype "passive"))
      (node (ref "BTN-UC-1") (pin "4A") (pinfunction "P$1_4A") (pintype "passive"))
      (node (ref "CB-485-1") (pin "1") (pinfunction "1_1") (pintype "passive"))
      (node (ref "CB-LCD-1") (pin "1") (pinfunction "1_1") (pintype "passive"))
      (node (ref "CB-UC-5") (pin "1") (pinfunction "1_1") (pintype "passive"))
      (node (ref "CF-LCD-1") (pin "1") (pinfunction "1_1") (pintype "passive"))
      (node (ref "CON-RPI") (pin "6") (pinfunction "GND_1_6") (pintype "power_in"))
      (node (ref "CON-RPI") (pin "9") (pinfunction "GND_2_9") (pintype "power_in"))
      (node (ref "CP-RPI-1") (pin "-") (pinfunction "-_-") (pintype "passive"))
      (node (ref "DL-UC-1") (pin "-") (pinfunction "-_-") (pintype "passive"))
      (node (ref "DL-UC-2") (pin "-") (pinfunction "-_-") (pintype "passive"))
      (node (ref "LF-485-2") (pin "1") (pinfunction "1_1") (pintype "passive"))
      (node (ref "LF-UC-3") (pin "1") (pinfunction "1_1") (pintype "passive"))
      (node (ref "MOD-LCD-1") (pin "1") (pinfunction "V-_1") (pintype "power_in"))
      (node (ref "MOD-LCD-1") (pin "10") (pinfunction "D3_10") (pintype "input"))
      (node (ref "MOD-LCD-1") (pin "16") (pinfunction "LIGHT-_16") (pintype "power_in"))
      (node (ref "MOD-LCD-1") (pin "7") (pinfunction "D0_7") (pintype "input"))
      (node (ref "MOD-LCD-1") (pin "8") (pinfunction "D1_8") (pintype "input"))
      (node (ref "MOD-LCD-1") (pin "9") (pinfunction "D2_9") (pintype "input"))
      (node (ref "MOD-PWR") (pin "V5.2-") (pinfunction "V5.2A3.0-_V5.2-") (pintype "power_in"))
      (node (ref "RD-LCD-1") (pin "1") (pinfunction "1_1") (pintype "passive"))
      (node (ref "RS-LCD-1") (pin "3A") (pinfunction "3A_3A") (pintype "bidirectional"))
    )
    (net (code "57") (name "/VSRVO#A+") (class "Default")
      (node (ref "IC-SRVO-1") (pin "1") (pinfunction "IIN_1") (pintype "power_in"))
      (node (ref "IC-SRVO-1") (pin "2") (pinfunction "IIN_2") (pintype "power_in"))
      (node (ref "MOD-PWR") (pin "V5.8+") (pinfunction "V5.8A3.0+_V5.8+") (pintype "power_in"))
    )
    (net (code "58") (name "/VSRVO#A-") (class "Default")
      (node (ref "CB-SRVO-2") (pin "1") (pinfunction "1_1") (pintype "passive"))
      (node (ref "LF-SRVO-2") (pin "1") (pinfunction "1_1") (pintype "passive"))
      (node (ref "MOD-PWR") (pin "V5.8-") (pinfunction "V5.8A3.0-_V5.8-") (pintype "power_in"))
    )
    (net (code "59") (name "/VSRVO#B+") (class "Default")
      (node (ref "F-SRVO-1") (pin "1") (pinfunction "1_1") (pintype "passive"))
      (node (ref "IC-SRVO-1") (pin "3") (pinfunction "IOUT_3") (pintype "power_in"))
      (node (ref "IC-SRVO-1") (pin "4") (pinfunction "IOUT_4") (pintype "power_in"))
      (node (ref "RU-SRVO-2") (pin "2") (pinfunction "2_2") (pintype "passive"))
    )
    (net (code "60") (name "/VSRVO#C+") (class "Default")
      (node (ref "CB-SRVO-2") (pin "2") (pinfunction "2_2") (pintype "passive"))
      (node (ref "LF-SRVO-1") (pin "1") (pinfunction "1_1") (pintype "passive"))
      (node (ref "TP-SRVO-1") (pin "3") (pinfunction "D_3") (pintype "passive"))
    )
    (net (code "61") (name "/VSRVO+") (class "Default")
      (node (ref "CB-SRVO-3") (pin "2") (pinfunction "2_2") (pintype "passive"))
      (node (ref "CB-SRVO-4") (pin "2") (pinfunction "2_2") (pintype "passive"))
      (node (ref "CON-SRVO") (pin "1+") (pinfunction "+_1+") (pintype "power_in"))
      (node (ref "CON-SRVO") (pin "2+") (pinfunction "+_2+") (pintype "power_in"))
      (node (ref "CON-SRVO") (pin "3+") (pinfunction "+_3+") (pintype "power_in"))
      (node (ref "CON-SRVO") (pin "4+") (pinfunction "+_4+") (pintype "power_in"))
      (node (ref "CON-SRVO") (pin "5+") (pinfunction "+_5+") (pintype "power_in"))
      (node (ref "CON-SRVO") (pin "6+") (pinfunction "+_6+") (pintype "power_in"))
      (node (ref "CON-SRVO") (pin "7+") (pinfunction "+_7+") (pintype "power_in"))
      (node (ref "CON-SRVO") (pin "8+") (pinfunction "+_8+") (pintype "power_in"))
      (node (ref "CP-SRVO-1") (pin "+") (pinfunction "+_+") (pintype "passive"))
      (node (ref "LF-SRVO-1") (pin "2") (pinfunction "2_2") (pintype "passive"))
      (node (ref "RD-SRVO-1") (pin "1") (pinfunction "1_1") (pintype "passive"))
    )
    (net (code "62") (name "/VSRVO-") (class "Default")
      (node (ref "CB-SRVO-3") (pin "1") (pinfunction "1_1") (pintype "passive"))
      (node (ref "CB-SRVO-4") (pin "1") (pinfunction "1_1") (pintype "passive"))
      (node (ref "CON-SRVO") (pin "1-") (pinfunction "-_1-") (pintype "power_in"))
      (node (ref "CON-SRVO") (pin "2-") (pinfunction "-_2-") (pintype "power_in"))
      (node (ref "CON-SRVO") (pin "3-") (pinfunction "-_3-") (pintype "power_in"))
      (node (ref "CON-SRVO") (pin "4-") (pinfunction "-_4-") (pintype "power_in"))
      (node (ref "CON-SRVO") (pin "5-") (pinfunction "-_5-") (pintype "power_in"))
      (node (ref "CON-SRVO") (pin "6-") (pinfunction "-_6-") (pintype "power_in"))
      (node (ref "CON-SRVO") (pin "7-") (pinfunction "-_7-") (pintype "power_in"))
      (node (ref "CON-SRVO") (pin "8-") (pinfunction "-_8-") (pintype "power_in"))
      (node (ref "CP-SRVO-1") (pin "-") (pinfunction "-_-") (pintype "passive"))
      (node (ref "DL-SRVO-1") (pin "-") (pinfunction "-_-") (pintype "passive"))
      (node (ref "LF-SRVO-2") (pin "2") (pinfunction "2_2") (pintype "passive"))
    )
    (net (code "63") (name "/VUC+") (class "Default")
      (node (ref "CB-UC-1") (pin "2") (pinfunction "2_2") (pintype "passive"))
      (node (ref "CB-UC-2") (pin "2") (pinfunction "2_2") (pintype "passive"))
      (node (ref "CB-UC-3") (pin "2") (pinfunction "2_2") (pintype "passive"))
      (node (ref "CB-UC-6") (pin "2") (pinfunction "2_2") (pintype "passive"))
      (node (ref "CON-UPDI") (pin "2") (pinfunction "2_2") (pintype "passive"))
      (node (ref "IC-UC-1") (pin "14") (pinfunction "VDD_14") (pintype "power_in"))
      (node (ref "IC-UC-1") (pin "42") (pinfunction "VDD_42") (pintype "power_in"))
      (node (ref "LF-UC-1") (pin "1") (pinfunction "1_1") (pintype "passive"))
      (node (ref "LF-UC-2") (pin "2") (pinfunction "2_2") (pintype "passive"))
      (node (ref "MOD-IMU-1") (pin "VCC") (pinfunction "VCC_VCC") (pintype "power_in"))
      (node (ref "RU-UC-1") (pin "2") (pinfunction "2_2") (pintype "passive"))
    )
    (net (code "64") (name "/VUC-") (class "Default")
      (node (ref "CB-IN-1") (pin "1") (pinfunction "1_1") (pintype "passive"))
      (node (ref "CB-RPI-1") (pin "1") (pinfunction "1_1") (pintype "passive"))
      (node (ref "CB-SRVO-1") (pin "1") (pinfunction "1_1") (pintype "passive"))
      (node (ref "CB-UC-1") (pin "1") (pinfunction "1_1") (pintype "passive"))
      (node (ref "CB-UC-2") (pin "1") (pinfunction "1_1") (pintype "passive"))
      (node (ref "CB-UC-3") (pin "1") (pinfunction "1_1") (pintype "passive"))
      (node (ref "CB-UC-4") (pin "1") (pinfunction "1_1") (pintype "passive"))
      (node (ref "CB-UC-6") (pin "1") (pinfunction "1_1") (pintype "passive"))
      (node (ref "CF-IN-1") (pin "1") (pinfunction "1_1") (pintype "passive"))
      (node (ref "CF-IN-2") (pin "1") (pinfunction "1_1") (pintype "passive"))
      (node (ref "CF-RPI-1") (pin "1") (pinfunction "1_1") (pintype "passive"))
      (node (ref "CF-RPI-2") (pin "1") (pinfunction "1_1") (pintype "passive"))
      (node (ref "CF-SRVO-1") (pin "1") (pinfunction "1_1") (pintype "passive"))
      (node (ref "CF-SRVO-2") (pin "1") (pinfunction "1_1") (pintype "passive"))
      (node (ref "CON-UPDI") (pin "1") (pinfunction "1_1") (pintype "passive"))
      (node (ref "IC-IN-1") (pin "5") (pinfunction "-_5") (pintype "power_in"))
      (node (ref "IC-RPI-1") (pin "5") (pinfunction "-_5") (pintype "power_in"))
      (node (ref "IC-SRVO-1") (pin "5") (pinfunction "-_5") (pintype "power_in"))
      (node (ref "IC-UC-1") (pin "15") (pinfunction "GND_15") (pintype "power_in"))
      (node (ref "IC-UC-1") (pin "29") (pinfunction "GND_29") (pintype "power_in"))
      (node (ref "IC-UC-1") (pin "43") (pinfunction "GND_43") (pintype "power_in"))
      (node (ref "LF-UC-3") (pin "2") (pinfunction "2_2") (pintype "passive"))
      (node (ref "MOD-IMU-1") (pin "COM") (pinfunction "COM_COM") (pintype "power_in"))
      (node (ref "RD-IN-1") (pin "1") (pinfunction "1_1") (pintype "passive"))
      (node (ref "RD-RPI-2") (pin "1") (pinfunction "1_1") (pintype "passive"))
      (node (ref "RD-SRVO-2") (pin "1") (pinfunction "1_1") (pintype "passive"))
      (node (ref "RD-UC-1") (pin "1") (pinfunction "1_1") (pintype "passive"))
      (node (ref "TN-UC-1") (pin "2") (pinfunction "S_2") (pintype "passive"))
    )
    (net (code "65") (name "Net-(CON-485-1-PadSHIELD)") (class "Default")
      (node (ref "CON-485-1") (pin "SHIELD") (pinfunction "SHIELD_SHIELD") (pintype "bidirectional"))
      (node (ref "RS-485-2") (pin "2") (pinfunction "2_2") (pintype "passive"))
    )
    (net (code "66") (name "Net-(CON-485-2-PadSHIELD)") (class "Default")
      (node (ref "CON-485-2") (pin "SHIELD") (pinfunction "SHIELD_SHIELD") (pintype "bidirectional"))
      (node (ref "RS-485-3") (pin "2") (pinfunction "2_2") (pintype "passive"))
    )
    (net (code "67") (name "Net-(CON-SRVO-Pad1)") (class "Default")
      (node (ref "CON-SRVO") (pin "1") (pinfunction "1_1") (pintype "input"))
      (node (ref "RS-SRVO-2") (pin "1A") (pinfunction "1A_1A") (pintype "bidirectional"))
    )
    (net (code "68") (name "Net-(CON-SRVO-Pad2)") (class "Default")
      (node (ref "CON-SRVO") (pin "2") (pinfunction "2_2") (pintype "input"))
      (node (ref "RS-SRVO-2") (pin "2A") (pinfunction "2A_2A") (pintype "bidirectional"))
    )
    (net (code "69") (name "Net-(CON-SRVO-Pad3)") (class "Default")
      (node (ref "CON-SRVO") (pin "3") (pinfunction "3_3") (pintype "input"))
      (node (ref "RS-SRVO-2") (pin "3A") (pinfunction "3A_3A") (pintype "bidirectional"))
    )
    (net (code "70") (name "Net-(CON-SRVO-Pad4)") (class "Default")
      (node (ref "CON-SRVO") (pin "4") (pinfunction "4_4") (pintype "input"))
      (node (ref "RS-SRVO-2") (pin "4A") (pinfunction "4A_4A") (pintype "bidirectional"))
    )
    (net (code "71") (name "Net-(CON-SRVO-Pad5)") (class "Default")
      (node (ref "CON-SRVO") (pin "5") (pinfunction "5_5") (pintype "input"))
      (node (ref "RS-SRVO-3") (pin "1A") (pinfunction "1A_1A") (pintype "bidirectional"))
    )
    (net (code "72") (name "Net-(CON-SRVO-Pad6)") (class "Default")
      (node (ref "CON-SRVO") (pin "6") (pinfunction "6_6") (pintype "input"))
      (node (ref "RS-SRVO-3") (pin "2A") (pinfunction "2A_2A") (pintype "bidirectional"))
    )
    (net (code "73") (name "Net-(CON-SRVO-Pad7)") (class "Default")
      (node (ref "CON-SRVO") (pin "7") (pinfunction "7_7") (pintype "input"))
      (node (ref "RS-SRVO-3") (pin "3A") (pinfunction "3A_3A") (pintype "bidirectional"))
    )
    (net (code "74") (name "Net-(CON-SRVO-Pad8)") (class "Default")
      (node (ref "CON-SRVO") (pin "8") (pinfunction "8_8") (pintype "input"))
      (node (ref "RS-SRVO-3") (pin "4A") (pinfunction "4A_4A") (pintype "bidirectional"))
    )
    (net (code "75") (name "Net-(DL-SRVO-1-Pad+)") (class "Default")
      (node (ref "DL-SRVO-1") (pin "+") (pinfunction "+_+") (pintype "passive"))
      (node (ref "RD-SRVO-1") (pin "2") (pinfunction "2_2") (pintype "passive"))
    )
    (net (code "76") (name "Net-(DL-UC-1-Pad+)") (class "Default")
      (node (ref "DL-UC-1") (pin "+") (pinfunction "+_+") (pintype "passive"))
      (node (ref "RS-UC-1") (pin "2") (pinfunction "2_2") (pintype "passive"))
    )
    (net (code "77") (name "Net-(DL-UC-2-Pad+)") (class "Default")
      (node (ref "DL-UC-2") (pin "+") (pinfunction "+_+") (pintype "passive"))
      (node (ref "RS-UC-2") (pin "2") (pinfunction "2_2") (pintype "passive"))
    )
    (net (code "78") (name "Net-(IC-485-1-RXEN#)") (class "Default")
      (node (ref "IC-485-1") (pin "2") (pinfunction "RXEN#_2") (pintype "input"))
      (node (ref "RS-485-1") (pin "2B") (pinfunction "2B_2B") (pintype "bidirectional"))
    )
    (net (code "79") (name "Net-(IC-485-1-RXO)") (class "Default")
      (node (ref "IC-485-1") (pin "1") (pinfunction "RXO_1") (pintype "output"))
      (node (ref "RS-485-1") (pin "1B") (pinfunction "1B_1B") (pintype "bidirectional"))
    )
    (net (code "80") (name "Net-(IC-485-1-TXEN)") (class "Default")
      (node (ref "IC-485-1") (pin "3") (pinfunction "TXEN_3") (pintype "input"))
      (node (ref "RS-485-1") (pin "3B") (pinfunction "3B_3B") (pintype "bidirectional"))
    )
    (net (code "81") (name "Net-(IC-485-1-TXI)") (class "Default")
      (node (ref "IC-485-1") (pin "4") (pinfunction "TXI_4") (pintype "input"))
      (node (ref "RS-485-1") (pin "4B") (pinfunction "4B_4B") (pintype "bidirectional"))
    )
    (net (code "82") (name "Net-(IC-IN-1-FILTER)") (class "Default")
      (node (ref "CF-IN-2") (pin "2") (pinfunction "2_2") (pintype "passive"))
      (node (ref "IC-IN-1") (pin "6") (pinfunction "FILTER_6") (pintype "passive"))
    )
    (net (code "83") (name "Net-(IC-RPI-1-FILTER)") (class "Default")
      (node (ref "CF-RPI-1") (pin "2") (pinfunction "2_2") (pintype "passive"))
      (node (ref "IC-RPI-1") (pin "6") (pinfunction "FILTER_6") (pintype "passive"))
    )
    (net (code "84") (name "Net-(IC-SRVO-1-FILTER)") (class "Default")
      (node (ref "CF-SRVO-1") (pin "2") (pinfunction "2_2") (pintype "passive"))
      (node (ref "IC-SRVO-1") (pin "6") (pinfunction "FILTER_6") (pintype "passive"))
    )
    (net (code "85") (name "Net-(MOD-LCD-1-D4)") (class "Default")
      (node (ref "MOD-LCD-1") (pin "11") (pinfunction "D4_11") (pintype "input"))
      (node (ref "RS-LCD-2") (pin "1B") (pinfunction "1B_1B") (pintype "bidirectional"))
    )
    (net (code "86") (name "Net-(MOD-LCD-1-D5)") (class "Default")
      (node (ref "MOD-LCD-1") (pin "12") (pinfunction "D5_12") (pintype "input"))
      (node (ref "RS-LCD-2") (pin "2B") (pinfunction "2B_2B") (pintype "bidirectional"))
    )
    (net (code "87") (name "Net-(MOD-LCD-1-D6)") (class "Default")
      (node (ref "MOD-LCD-1") (pin "13") (pinfunction "D6_13") (pintype "input"))
      (node (ref "RS-LCD-2") (pin "3B") (pinfunction "3B_3B") (pintype "bidirectional"))
    )
    (net (code "88") (name "Net-(MOD-LCD-1-D7)") (class "Default")
      (node (ref "MOD-LCD-1") (pin "14") (pinfunction "D7_14") (pintype "input"))
      (node (ref "RS-LCD-2") (pin "4B") (pinfunction "4B_4B") (pintype "bidirectional"))
    )
    (net (code "89") (name "Net-(MOD-LCD-1-E)") (class "Default")
      (node (ref "MOD-LCD-1") (pin "6") (pinfunction "E_6") (pintype "input"))
      (node (ref "RS-LCD-1") (pin "4B") (pinfunction "4B_4B") (pintype "bidirectional"))
    )
    (net (code "90") (name "Net-(MOD-LCD-1-RS)") (class "Default")
      (node (ref "MOD-LCD-1") (pin "4") (pinfunction "RS_4") (pintype "input"))
      (node (ref "RS-LCD-1") (pin "2B") (pinfunction "2B_2B") (pintype "bidirectional"))
    )
    (net (code "91") (name "Net-(MOD-LCD-1-R{slash}W)") (class "Default")
      (node (ref "MOD-LCD-1") (pin "5") (pinfunction "R/W_5") (pintype "input"))
      (node (ref "RS-LCD-1") (pin "3B") (pinfunction "3B_3B") (pintype "bidirectional"))
    )
    (net (code "92") (name "Net-(TP-SRVO-1-G)") (class "Default")
      (node (ref "RS-SRVO-1") (pin "2") (pinfunction "2_2") (pintype "passive"))
      (node (ref "RU-SRVO-1") (pin "2") (pinfunction "2_2") (pintype "passive"))
      (node (ref "TP-SRVO-1") (pin "1") (pinfunction "G_1") (pintype "passive"))
    )
    (net (code "93") (name "Net-(TP-SRVO-1-S)") (class "Default")
      (node (ref "F-SRVO-1") (pin "2") (pinfunction "2_2") (pintype "passive"))
      (node (ref "RU-SRVO-1") (pin "1") (pinfunction "1_1") (pintype "passive"))
      (node (ref "TP-SRVO-1") (pin "2") (pinfunction "S_2") (pintype "passive"))
    )
    (net (code "94") (name "unconnected-(CON-RPI-SCL-Pad5)") (class "Default")
      (node (ref "CON-RPI") (pin "5") (pinfunction "SCL_5") (pintype "bidirectional"))
    )
    (net (code "95") (name "unconnected-(CON-RPI-SDA-Pad3)") (class "Default")
      (node (ref "CON-RPI") (pin "3") (pinfunction "SDA_3") (pintype "bidirectional"))
    )
    (net (code "96") (name "unconnected-(IC-UC-1-PC6{slash}1,XCK{slash}1-OUT-Pad18)") (class "Default")
      (node (ref "IC-UC-1") (pin "18") (pinfunction "PC6/1,XCK/1-OUT_18") (pintype "bidirectional"))
    )
    (net (code "97") (name "unconnected-(IC-UC-1-PC7{slash}1,XDIR{slash}EVOUTC-Pad19)") (class "Default")
      (node (ref "IC-UC-1") (pin "19") (pinfunction "PC7/1,XDIR/EVOUTC_19") (pintype "bidirectional"))
    )
    (net (code "98") (name "unconnected-(IC-UC-1-PD6{slash}AIN6{slash}P2{slash}2-OUT-Pad26)") (class "Default")
      (node (ref "IC-UC-1") (pin "26") (pinfunction "PD6/AIN6/P2/2-OUT_26") (pintype "bidirectional"))
    )
    (net (code "99") (name "unconnected-(IC-UC-1-PF4{slash}AIN14{slash}2,TXD{slash}0-WO4{slash}0-WO-Pad38)") (class "Default")
      (node (ref "IC-UC-1") (pin "38") (pinfunction "PF4/AIN14/2,TXD/0-WO4/0-WO_38") (pintype "bidirectional"))
    )
    (net (code "100") (name "unconnected-(IC-UC-1-PF5{slash}AIN15{slash}2,RXD{slash}0-WO5{slash}1-WO-Pad39)") (class "Default")
      (node (ref "IC-UC-1") (pin "39") (pinfunction "PF5/AIN15/2,RXD/0-WO5/1-WO_39") (pintype "bidirectional"))
    )
    (net (code "101") (name "unconnected-(RS-RPI-1-Pad4A)") (class "Default")
      (node (ref "RS-RPI-1") (pin "4A") (pinfunction "4A_4A") (pintype "bidirectional"))
    )
    (net (code "102") (name "unconnected-(RS-RPI-1-Pad4B)") (class "Default")
      (node (ref "RS-RPI-1") (pin "4B") (pinfunction "4B_4B") (pintype "bidirectional"))
    )
  )
)
